# board.net
KiCad netlist of a schematic drawn in EAGLE
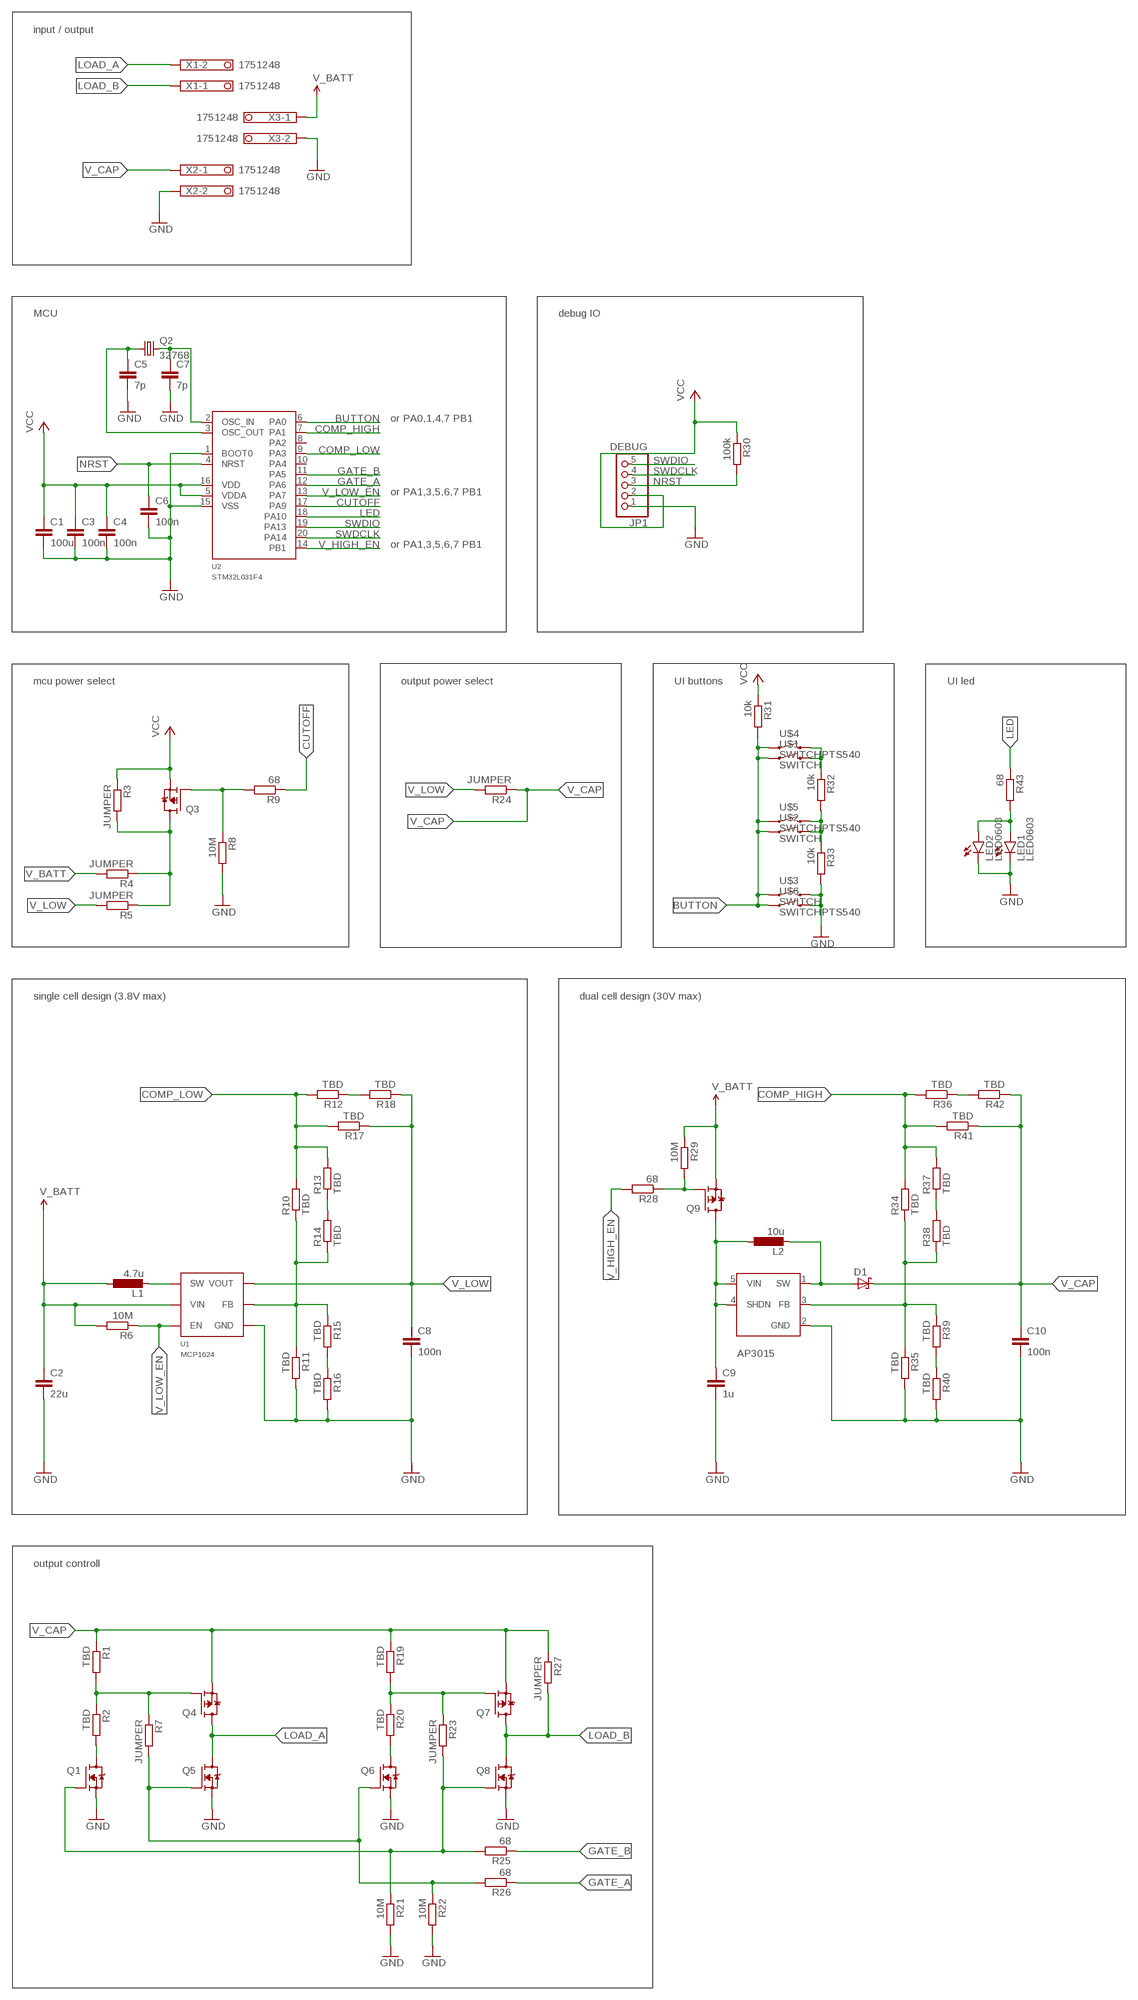
[diagram p0: schematic, sheet 1]

(export (version "E")
  (design (tool "Eeschema 10.0.6"))
  (components
    (comp (ref "C1")
      (value "100u")
      (footprint "eagle-import:1206-SMALL")
      (libsource (lib "eagle-import") (part "CAPACITOR1206"))
    )
    (comp (ref "C2")
      (value "22u")
      (footprint "eagle-import:0805-SMALL")
      (libsource (lib "eagle-import") (part "CAPACITOR0805"))
    )
    (comp (ref "C3")
      (value "100n")
      (footprint "eagle-import:0603-SMALL")
      (libsource (lib "eagle-import") (part "CAPACITOR0603"))
    )
    (comp (ref "C4")
      (value "100n")
      (footprint "eagle-import:0603-SMALL")
      (libsource (lib "eagle-import") (part "CAPACITOR0603"))
    )
    (comp (ref "C5")
      (value "7p")
      (footprint "eagle-import:0603-SMALL")
      (libsource (lib "eagle-import") (part "C-EU0603-SAMLL"))
    )
    (comp (ref "C6")
      (value "100n")
      (footprint "eagle-import:0603-SMALL")
      (libsource (lib "eagle-import") (part "CAPACITOR0603"))
    )
    (comp (ref "C7")
      (value "7p")
      (footprint "eagle-import:0603-SMALL")
      (libsource (lib "eagle-import") (part "C-EU0603-SAMLL"))
    )
    (comp (ref "C8")
      (value "100n")
      (footprint "eagle-import:0603-SMALL")
      (libsource (lib "eagle-import") (part "CAPACITOR0603"))
    )
    (comp (ref "C9")
      (value "1u")
      (footprint "eagle-import:0805-SMALL")
      (libsource (lib "eagle-import") (part "CAPACITOR0805"))
    )
    (comp (ref "C10")
      (value "100n")
      (footprint "eagle-import:0603-SMALL")
      (libsource (lib "eagle-import") (part "CAPACITOR0603"))
    )
    (comp (ref "D1")
      (value "SCHOTTKY")
      (footprint "eagle-import:DO-214")
      (libsource (lib "eagle-import") (part "SCHOTTKY"))
    )
    (comp (ref "JP1")
      (value "DEBUG")
      (footprint "eagle-import:1X05-S")
      (libsource (lib "eagle-import") (part "PINHD-1X05_2.54-S"))
    )
    (comp (ref "L1")
      (value "4.7u")
      (footprint "eagle-import:SRN2510F")
      (libsource (lib "eagle-import") (part "INDUCTORSRN2510F"))
    )
    (comp (ref "L2")
      (value "10u")
      (footprint "eagle-import:74404043100A")
      (libsource (lib "eagle-import") (part "INDUCTOR74404043100A"))
    )
    (comp (ref "LED1")
      (value "LED0603")
      (footprint "eagle-import:0603-SMALL")
      (libsource (lib "eagle-import") (part "LED0603"))
    )
    (comp (ref "LED2")
      (value "LED0603")
      (footprint "eagle-import:0603-SMALL")
      (libsource (lib "eagle-import") (part "LED0603"))
    )
    (comp (ref "Q1")
      (value "NFETGENERIC")
      (footprint "eagle-import:SOT23")
      (libsource (lib "eagle-import") (part "NFETGENERIC"))
    )
    (comp (ref "Q2")
      (value "32768")
      (footprint "eagle-import:ABS07")
      (libsource (lib "eagle-import") (part "ABS07"))
    )
    (comp (ref "Q3")
      (value "PFETIRLML6401")
      (footprint "eagle-import:SOT23")
      (libsource (lib "eagle-import") (part "PFETIRLML6401"))
    )
    (comp (ref "Q4")
      (value "PFETIRLML6401")
      (footprint "eagle-import:SOT23")
      (libsource (lib "eagle-import") (part "PFETIRLML6401"))
    )
    (comp (ref "Q5")
      (value "NFETGENERIC")
      (footprint "eagle-import:SOT23")
      (libsource (lib "eagle-import") (part "NFETGENERIC"))
    )
    (comp (ref "Q6")
      (value "NFETGENERIC")
      (footprint "eagle-import:SOT23")
      (libsource (lib "eagle-import") (part "NFETGENERIC"))
    )
    (comp (ref "Q7")
      (value "PFETIRLML6401")
      (footprint "eagle-import:SOT23")
      (libsource (lib "eagle-import") (part "PFETIRLML6401"))
    )
    (comp (ref "Q8")
      (value "NFETGENERIC")
      (footprint "eagle-import:SOT23")
      (libsource (lib "eagle-import") (part "NFETGENERIC"))
    )
    (comp (ref "Q9")
      (value "PFETIRLML6401")
      (footprint "eagle-import:SOT23")
      (libsource (lib "eagle-import") (part "PFETIRLML6401"))
    )
    (comp (ref "R1")
      (value "TBD")
      (footprint "eagle-import:0603-SMALL")
      (libsource (lib "eagle-import") (part "RESISTOR0603"))
    )
    (comp (ref "R2")
      (value "TBD")
      (footprint "eagle-import:0603-SMALL")
      (libsource (lib "eagle-import") (part "RESISTOR0603"))
    )
    (comp (ref "R3")
      (value "JUMPER")
      (footprint "eagle-import:0603-SMALL")
      (libsource (lib "eagle-import") (part "RESISTOR0603"))
    )
    (comp (ref "R4")
      (value "JUMPER")
      (footprint "eagle-import:0603-SMALL")
      (libsource (lib "eagle-import") (part "RESISTOR0603"))
    )
    (comp (ref "R5")
      (value "JUMPER")
      (footprint "eagle-import:0603-SMALL")
      (libsource (lib "eagle-import") (part "RESISTOR0603"))
    )
    (comp (ref "R6")
      (value "10M")
      (footprint "eagle-import:0603-SMALL")
      (libsource (lib "eagle-import") (part "RESISTOR0603"))
    )
    (comp (ref "R7")
      (value "JUMPER")
      (footprint "eagle-import:0603-SMALL")
      (libsource (lib "eagle-import") (part "RESISTOR0603"))
    )
    (comp (ref "R8")
      (value "10M")
      (footprint "eagle-import:0603-SMALL")
      (libsource (lib "eagle-import") (part "RESISTOR0603"))
    )
    (comp (ref "R9")
      (value "68")
      (footprint "eagle-import:0603-SMALL")
      (libsource (lib "eagle-import") (part "RESISTOR0603"))
    )
    (comp (ref "R10")
      (value "TBD")
      (footprint "eagle-import:0603-SMALL")
      (libsource (lib "eagle-import") (part "RESISTOR0603"))
    )
    (comp (ref "R11")
      (value "TBD")
      (footprint "eagle-import:0603-SMALL")
      (libsource (lib "eagle-import") (part "RESISTOR0603"))
    )
    (comp (ref "R12")
      (value "TBD")
      (footprint "eagle-import:0603-SMALL")
      (libsource (lib "eagle-import") (part "RESISTOR0603"))
    )
    (comp (ref "R13")
      (value "TBD")
      (footprint "eagle-import:0603-SMALL")
      (libsource (lib "eagle-import") (part "RESISTOR0603"))
    )
    (comp (ref "R14")
      (value "TBD")
      (footprint "eagle-import:0603-SMALL")
      (libsource (lib "eagle-import") (part "RESISTOR0603"))
    )
    (comp (ref "R15")
      (value "TBD")
      (footprint "eagle-import:0603-SMALL")
      (libsource (lib "eagle-import") (part "RESISTOR0603"))
    )
    (comp (ref "R16")
      (value "TBD")
      (footprint "eagle-import:0603-SMALL")
      (libsource (lib "eagle-import") (part "RESISTOR0603"))
    )
    (comp (ref "R17")
      (value "TBD")
      (footprint "eagle-import:0603-SMALL")
      (libsource (lib "eagle-import") (part "RESISTOR0603"))
    )
    (comp (ref "R18")
      (value "TBD")
      (footprint "eagle-import:0603-SMALL")
      (libsource (lib "eagle-import") (part "RESISTOR0603"))
    )
    (comp (ref "R19")
      (value "TBD")
      (footprint "eagle-import:0603-SMALL")
      (libsource (lib "eagle-import") (part "RESISTOR0603"))
    )
    (comp (ref "R20")
      (value "TBD")
      (footprint "eagle-import:0603-SMALL")
      (libsource (lib "eagle-import") (part "RESISTOR0603"))
    )
    (comp (ref "R21")
      (value "10M")
      (footprint "eagle-import:0603-SMALL")
      (libsource (lib "eagle-import") (part "RESISTOR0603"))
    )
    (comp (ref "R22")
      (value "10M")
      (footprint "eagle-import:0603-SMALL")
      (libsource (lib "eagle-import") (part "RESISTOR0603"))
    )
    (comp (ref "R23")
      (value "JUMPER")
      (footprint "eagle-import:0603-SMALL")
      (libsource (lib "eagle-import") (part "RESISTOR0603"))
    )
    (comp (ref "R24")
      (value "JUMPER")
      (footprint "eagle-import:0603-SMALL")
      (libsource (lib "eagle-import") (part "RESISTOR0603"))
    )
    (comp (ref "R25")
      (value "68")
      (footprint "eagle-import:0603-SMALL")
      (libsource (lib "eagle-import") (part "RESISTOR0603"))
    )
    (comp (ref "R26")
      (value "68")
      (footprint "eagle-import:0603-SMALL")
      (libsource (lib "eagle-import") (part "RESISTOR0603"))
    )
    (comp (ref "R27")
      (value "JUMPER")
      (footprint "eagle-import:0603-SMALL")
      (libsource (lib "eagle-import") (part "RESISTOR0603"))
    )
    (comp (ref "R28")
      (value "68")
      (footprint "eagle-import:0603-SMALL")
      (libsource (lib "eagle-import") (part "RESISTOR0603"))
    )
    (comp (ref "R29")
      (value "10M")
      (footprint "eagle-import:0603-SMALL")
      (libsource (lib "eagle-import") (part "RESISTOR0603"))
    )
    (comp (ref "R30")
      (value "100k")
      (footprint "eagle-import:0603-SMALL")
      (libsource (lib "eagle-import") (part "RESISTOR0603"))
    )
    (comp (ref "R31")
      (value "10k")
      (footprint "eagle-import:0603-SMALL")
      (libsource (lib "eagle-import") (part "RESISTOR0603"))
    )
    (comp (ref "R32")
      (value "10k")
      (footprint "eagle-import:0603-SMALL")
      (libsource (lib "eagle-import") (part "RESISTOR0603"))
    )
    (comp (ref "R33")
      (value "10k")
      (footprint "eagle-import:0603-SMALL")
      (libsource (lib "eagle-import") (part "RESISTOR0603"))
    )
    (comp (ref "R34")
      (value "TBD")
      (footprint "eagle-import:0603-SMALL")
      (libsource (lib "eagle-import") (part "RESISTOR0603"))
    )
    (comp (ref "R35")
      (value "TBD")
      (footprint "eagle-import:0603-SMALL")
      (libsource (lib "eagle-import") (part "RESISTOR0603"))
    )
    (comp (ref "R36")
      (value "TBD")
      (footprint "eagle-import:0603-SMALL")
      (libsource (lib "eagle-import") (part "RESISTOR0603"))
    )
    (comp (ref "R37")
      (value "TBD")
      (footprint "eagle-import:0603-SMALL")
      (libsource (lib "eagle-import") (part "RESISTOR0603"))
    )
    (comp (ref "R38")
      (value "TBD")
      (footprint "eagle-import:0603-SMALL")
      (libsource (lib "eagle-import") (part "RESISTOR0603"))
    )
    (comp (ref "R39")
      (value "TBD")
      (footprint "eagle-import:0603-SMALL")
      (libsource (lib "eagle-import") (part "RESISTOR0603"))
    )
    (comp (ref "R40")
      (value "TBD")
      (footprint "eagle-import:0603-SMALL")
      (libsource (lib "eagle-import") (part "RESISTOR0603"))
    )
    (comp (ref "R41")
      (value "TBD")
      (footprint "eagle-import:0603-SMALL")
      (libsource (lib "eagle-import") (part "RESISTOR0603"))
    )
    (comp (ref "R42")
      (value "TBD")
      (footprint "eagle-import:0603-SMALL")
      (libsource (lib "eagle-import") (part "RESISTOR0603"))
    )
    (comp (ref "R43")
      (value "68")
      (footprint "eagle-import:0603-SMALL")
      (libsource (lib "eagle-import") (part "RESISTOR0603"))
    )
    (comp (ref "U$1")
      (value "SWITCH")
      (footprint "eagle-import:TACT-4.6X2.8")
      (libsource (lib "eagle-import") (part "SWITCH"))
    )
    (comp (ref "U$2")
      (value "SWITCH")
      (footprint "eagle-import:TACT-4.6X2.8")
      (libsource (lib "eagle-import") (part "SWITCH"))
    )
    (comp (ref "U$3")
      (value "SWITCH")
      (footprint "eagle-import:TACT-4.6X2.8")
      (libsource (lib "eagle-import") (part "SWITCH"))
    )
    (comp (ref "U$4")
      (value "SWITCHPTS540")
      (footprint "eagle-import:PTS540")
      (libsource (lib "eagle-import") (part "SWITCHPTS540"))
    )
    (comp (ref "U$5")
      (value "SWITCHPTS540")
      (footprint "eagle-import:PTS540")
      (libsource (lib "eagle-import") (part "SWITCHPTS540"))
    )
    (comp (ref "U$6")
      (value "SWITCHPTS540")
      (footprint "eagle-import:PTS540")
      (libsource (lib "eagle-import") (part "SWITCHPTS540"))
    )
    (comp (ref "U1")
      (value "MCP1624")
      (footprint "eagle-import:SOT23-6")
      (libsource (lib "eagle-import") (part "MCP1624"))
    )
    (comp (ref "U2")
      (value "STM32L031F4")
      (footprint "eagle-import:TSSOP20")
      (libsource (lib "eagle-import") (part "STM32L031F4"))
    )
    (comp (ref "U3")
      (value "AP3015")
      (footprint "eagle-import:SOT23-5")
      (libsource (lib "eagle-import") (part "AP3015"))
    )
    (comp (ref "X1")
      (value "1751248")
      (footprint "eagle-import:1751248")
      (libsource (lib "eagle-import") (part "1751248"))
    )
    (comp (ref "X2")
      (value "1751248")
      (footprint "eagle-import:1751248")
      (libsource (lib "eagle-import") (part "1751248"))
    )
    (comp (ref "X3")
      (value "1751248")
      (footprint "eagle-import:1751248")
      (libsource (lib "eagle-import") (part "1751248"))
    )
  )
  (nets
    (net (code "1") (name "/SWDCLK") (class "Default")
      (node (ref "JP1") (pin "4") (pinfunction "4_4") (pintype "passive"))
      (node (ref "U2") (pin "20") (pinfunction "PA14_20") (pintype "bidirectional"))
    )
    (net (code "2") (name "/SWDIO") (class "Default")
      (node (ref "JP1") (pin "5") (pinfunction "5_5") (pintype "passive"))
      (node (ref "U2") (pin "19") (pinfunction "PA13_19") (pintype "bidirectional"))
    )
    (net (code "3") (name "BUTTON") (class "Default")
      (node (ref "R31") (pin "2") (pinfunction "2_2") (pintype "passive"))
      (node (ref "U$1") (pin "P$1") (pinfunction "1_P$1") (pintype "passive"))
      (node (ref "U$1") (pin "P$2") (pinfunction "1_P$2") (pintype "passive"))
      (node (ref "U$2") (pin "P$1") (pinfunction "1_P$1") (pintype "passive"))
      (node (ref "U$2") (pin "P$2") (pinfunction "1_P$2") (pintype "passive"))
      (node (ref "U$3") (pin "P$1") (pinfunction "1_P$1") (pintype "passive"))
      (node (ref "U$3") (pin "P$2") (pinfunction "1_P$2") (pintype "passive"))
      (node (ref "U$4") (pin "1") (pinfunction "1_1") (pintype "passive"))
      (node (ref "U$4") (pin "2") (pinfunction "1_2") (pintype "passive"))
      (node (ref "U$5") (pin "1") (pinfunction "1_1") (pintype "passive"))
      (node (ref "U$5") (pin "2") (pinfunction "1_2") (pintype "passive"))
      (node (ref "U$6") (pin "1") (pinfunction "1_1") (pintype "passive"))
      (node (ref "U$6") (pin "2") (pinfunction "1_2") (pintype "passive"))
      (node (ref "U2") (pin "6") (pinfunction "PA0_6") (pintype "bidirectional"))
    )
    (net (code "4") (name "COMP_HIGH") (class "Default")
      (node (ref "R34") (pin "2") (pinfunction "2_2") (pintype "passive"))
      (node (ref "R36") (pin "2") (pinfunction "2_2") (pintype "passive"))
      (node (ref "R37") (pin "2") (pinfunction "2_2") (pintype "passive"))
      (node (ref "R41") (pin "2") (pinfunction "2_2") (pintype "passive"))
      (node (ref "U2") (pin "7") (pinfunction "PA1_7") (pintype "bidirectional"))
    )
    (net (code "5") (name "COMP_LOW") (class "Default")
      (node (ref "R10") (pin "2") (pinfunction "2_2") (pintype "passive"))
      (node (ref "R12") (pin "2") (pinfunction "2_2") (pintype "passive"))
      (node (ref "R13") (pin "2") (pinfunction "2_2") (pintype "passive"))
      (node (ref "R17") (pin "2") (pinfunction "2_2") (pintype "passive"))
      (node (ref "U2") (pin "9") (pinfunction "PA3_9") (pintype "bidirectional"))
    )
    (net (code "6") (name "CUTOFF") (class "Default")
      (node (ref "R9") (pin "1") (pinfunction "1_1") (pintype "passive"))
      (node (ref "U2") (pin "17") (pinfunction "PA9_17") (pintype "bidirectional"))
    )
    (net (code "7") (name "GATE_A") (class "Default")
      (node (ref "R26") (pin "1") (pinfunction "1_1") (pintype "passive"))
      (node (ref "U2") (pin "12") (pinfunction "PA6_12") (pintype "bidirectional"))
    )
    (net (code "8") (name "GATE_B") (class "Default")
      (node (ref "R25") (pin "1") (pinfunction "1_1") (pintype "passive"))
      (node (ref "U2") (pin "11") (pinfunction "PA5_11") (pintype "bidirectional"))
    )
    (net (code "9") (name "GND") (class "Default")
      (node (ref "C1") (pin "2") (pinfunction "2_2") (pintype "passive"))
      (node (ref "C10") (pin "2") (pinfunction "2_2") (pintype "passive"))
      (node (ref "C2") (pin "2") (pinfunction "2_2") (pintype "passive"))
      (node (ref "C3") (pin "2") (pinfunction "2_2") (pintype "passive"))
      (node (ref "C4") (pin "2") (pinfunction "2_2") (pintype "passive"))
      (node (ref "C5") (pin "2") (pinfunction "2_2") (pintype "passive"))
      (node (ref "C6") (pin "2") (pinfunction "2_2") (pintype "passive"))
      (node (ref "C7") (pin "2") (pinfunction "2_2") (pintype "passive"))
      (node (ref "C8") (pin "2") (pinfunction "2_2") (pintype "passive"))
      (node (ref "C9") (pin "2") (pinfunction "2_2") (pintype "passive"))
      (node (ref "JP1") (pin "1") (pinfunction "1_1") (pintype "passive"))
      (node (ref "LED1") (pin "2") (pinfunction "C_2") (pintype "passive"))
      (node (ref "LED2") (pin "2") (pinfunction "C_2") (pintype "passive"))
      (node (ref "Q1") (pin "2") (pinfunction "S_2") (pintype "passive"))
      (node (ref "Q5") (pin "2") (pinfunction "S_2") (pintype "passive"))
      (node (ref "Q6") (pin "2") (pinfunction "S_2") (pintype "passive"))
      (node (ref "Q8") (pin "2") (pinfunction "S_2") (pintype "passive"))
      (node (ref "R11") (pin "2") (pinfunction "2_2") (pintype "passive"))
      (node (ref "R16") (pin "2") (pinfunction "2_2") (pintype "passive"))
      (node (ref "R21") (pin "2") (pinfunction "2_2") (pintype "passive"))
      (node (ref "R22") (pin "2") (pinfunction "2_2") (pintype "passive"))
      (node (ref "R33") (pin "2") (pinfunction "2_2") (pintype "passive"))
      (node (ref "R35") (pin "2") (pinfunction "2_2") (pintype "passive"))
      (node (ref "R40") (pin "2") (pinfunction "2_2") (pintype "passive"))
      (node (ref "R8") (pin "2") (pinfunction "2_2") (pintype "passive"))
      (node (ref "U$3") (pin "P$3") (pinfunction "2_P$3") (pintype "passive"))
      (node (ref "U$3") (pin "P$4") (pinfunction "2_P$4") (pintype "passive"))
      (node (ref "U$6") (pin "3") (pinfunction "2_3") (pintype "passive"))
      (node (ref "U$6") (pin "4") (pinfunction "2_4") (pintype "passive"))
      (node (ref "U1") (pin "2") (pinfunction "GND_2") (pintype "bidirectional"))
      (node (ref "U2") (pin "1") (pinfunction "BOOT0_1") (pintype "bidirectional"))
      (node (ref "U2") (pin "15") (pinfunction "VSS_15") (pintype "bidirectional"))
      (node (ref "U3") (pin "2") (pinfunction "GND_2") (pintype "bidirectional"))
      (node (ref "X2") (pin "2") (pinfunction "K_2") (pintype "passive"))
      (node (ref "X3") (pin "2") (pinfunction "K_2") (pintype "passive"))
    )
    (net (code "10") (name "LED") (class "Default")
      (node (ref "R43") (pin "1") (pinfunction "1_1") (pintype "passive"))
      (node (ref "U2") (pin "18") (pinfunction "PA10_18") (pintype "bidirectional"))
    )
    (net (code "11") (name "LOAD_A") (class "Default")
      (node (ref "Q4") (pin "3") (pinfunction "D_3") (pintype "passive"))
      (node (ref "Q5") (pin "3") (pinfunction "D_3") (pintype "passive"))
      (node (ref "X1") (pin "2") (pinfunction "K_2") (pintype "passive"))
    )
    (net (code "12") (name "LOAD_B") (class "Default")
      (node (ref "Q7") (pin "3") (pinfunction "D_3") (pintype "passive"))
      (node (ref "Q8") (pin "3") (pinfunction "D_3") (pintype "passive"))
      (node (ref "R27") (pin "2") (pinfunction "2_2") (pintype "passive"))
      (node (ref "X1") (pin "1") (pinfunction "K_1") (pintype "passive"))
    )
    (net (code "13") (name "NRST") (class "Default")
      (node (ref "C6") (pin "1") (pinfunction "1_1") (pintype "passive"))
      (node (ref "JP1") (pin "3") (pinfunction "3_3") (pintype "passive"))
      (node (ref "R30") (pin "2") (pinfunction "2_2") (pintype "passive"))
      (node (ref "U2") (pin "4") (pinfunction "NRST_4") (pintype "bidirectional"))
    )
    (net (code "14") (name "Net-(D1-A)") (class "Default")
      (node (ref "D1") (pin "P$1") (pinfunction "A_P$1") (pintype "passive"))
      (node (ref "L2") (pin "P$2") (pinfunction "2_P$2") (pintype "passive"))
      (node (ref "U3") (pin "1") (pinfunction "SW_1") (pintype "bidirectional"))
    )
    (net (code "15") (name "Net-(L1-2)") (class "Default")
      (node (ref "L1") (pin "P$2") (pinfunction "2_P$2") (pintype "passive"))
      (node (ref "U1") (pin "1") (pinfunction "SW_1") (pintype "bidirectional"))
    )
    (net (code "16") (name "Net-(L2-1)") (class "Default")
      (node (ref "C9") (pin "1") (pinfunction "1_1") (pintype "passive"))
      (node (ref "L2") (pin "P$1") (pinfunction "1_P$1") (pintype "passive"))
      (node (ref "Q9") (pin "3") (pinfunction "D_3") (pintype "passive"))
      (node (ref "U3") (pin "4") (pinfunction "SHDN_4") (pintype "bidirectional"))
      (node (ref "U3") (pin "5") (pinfunction "VIN_5") (pintype "bidirectional"))
    )
    (net (code "17") (name "Net-(LED1-A)") (class "Default")
      (node (ref "LED1") (pin "1") (pinfunction "A_1") (pintype "passive"))
      (node (ref "LED2") (pin "1") (pinfunction "A_1") (pintype "passive"))
      (node (ref "R43") (pin "2") (pinfunction "2_2") (pintype "passive"))
    )
    (net (code "18") (name "Net-(Q1-D)") (class "Default")
      (node (ref "Q1") (pin "3") (pinfunction "D_3") (pintype "passive"))
      (node (ref "R2") (pin "2") (pinfunction "2_2") (pintype "passive"))
    )
    (net (code "19") (name "Net-(Q1-G)") (class "Default")
      (node (ref "Q1") (pin "1") (pinfunction "G_1") (pintype "passive"))
      (node (ref "Q8") (pin "1") (pinfunction "G_1") (pintype "passive"))
      (node (ref "R21") (pin "1") (pinfunction "1_1") (pintype "passive"))
      (node (ref "R23") (pin "2") (pinfunction "2_2") (pintype "passive"))
      (node (ref "R25") (pin "2") (pinfunction "2_2") (pintype "passive"))
    )
    (net (code "20") (name "Net-(Q2-1)") (class "Default")
      (node (ref "C5") (pin "1") (pinfunction "1_1") (pintype "passive"))
      (node (ref "Q2") (pin "P$1") (pinfunction "1_P$1") (pintype "passive"))
      (node (ref "U2") (pin "3") (pinfunction "OSC_OUT_3") (pintype "bidirectional"))
    )
    (net (code "21") (name "Net-(Q2-2)") (class "Default")
      (node (ref "C7") (pin "1") (pinfunction "1_1") (pintype "passive"))
      (node (ref "Q2") (pin "P$2") (pinfunction "2_P$2") (pintype "passive"))
      (node (ref "U2") (pin "2") (pinfunction "OSC_IN_2") (pintype "bidirectional"))
    )
    (net (code "22") (name "Net-(Q3-D)") (class "Default")
      (node (ref "Q3") (pin "3") (pinfunction "D_3") (pintype "passive"))
      (node (ref "R3") (pin "2") (pinfunction "2_2") (pintype "passive"))
      (node (ref "R4") (pin "1") (pinfunction "1_1") (pintype "passive"))
      (node (ref "R5") (pin "1") (pinfunction "1_1") (pintype "passive"))
    )
    (net (code "23") (name "Net-(Q3-G)") (class "Default")
      (node (ref "Q3") (pin "1") (pinfunction "G_1") (pintype "passive"))
      (node (ref "R8") (pin "1") (pinfunction "1_1") (pintype "passive"))
      (node (ref "R9") (pin "2") (pinfunction "2_2") (pintype "passive"))
    )
    (net (code "24") (name "Net-(Q4-G)") (class "Default")
      (node (ref "Q4") (pin "1") (pinfunction "G_1") (pintype "passive"))
      (node (ref "R1") (pin "2") (pinfunction "2_2") (pintype "passive"))
      (node (ref "R2") (pin "1") (pinfunction "1_1") (pintype "passive"))
      (node (ref "R7") (pin "1") (pinfunction "1_1") (pintype "passive"))
    )
    (net (code "25") (name "Net-(Q5-G)") (class "Default")
      (node (ref "Q5") (pin "1") (pinfunction "G_1") (pintype "passive"))
      (node (ref "Q6") (pin "1") (pinfunction "G_1") (pintype "passive"))
      (node (ref "R22") (pin "1") (pinfunction "1_1") (pintype "passive"))
      (node (ref "R26") (pin "2") (pinfunction "2_2") (pintype "passive"))
      (node (ref "R7") (pin "2") (pinfunction "2_2") (pintype "passive"))
    )
    (net (code "26") (name "Net-(Q6-D)") (class "Default")
      (node (ref "Q6") (pin "3") (pinfunction "D_3") (pintype "passive"))
      (node (ref "R20") (pin "2") (pinfunction "2_2") (pintype "passive"))
    )
    (net (code "27") (name "Net-(Q7-G)") (class "Default")
      (node (ref "Q7") (pin "1") (pinfunction "G_1") (pintype "passive"))
      (node (ref "R19") (pin "2") (pinfunction "2_2") (pintype "passive"))
      (node (ref "R20") (pin "1") (pinfunction "1_1") (pintype "passive"))
      (node (ref "R23") (pin "1") (pinfunction "1_1") (pintype "passive"))
    )
    (net (code "28") (name "Net-(Q9-G)") (class "Default")
      (node (ref "Q9") (pin "1") (pinfunction "G_1") (pintype "passive"))
      (node (ref "R28") (pin "1") (pinfunction "1_1") (pintype "passive"))
      (node (ref "R29") (pin "2") (pinfunction "2_2") (pintype "passive"))
    )
    (net (code "29") (name "Net-(R12-Pad1)") (class "Default")
      (node (ref "R12") (pin "1") (pinfunction "1_1") (pintype "passive"))
      (node (ref "R18") (pin "2") (pinfunction "2_2") (pintype "passive"))
    )
    (net (code "30") (name "Net-(R13-Pad1)") (class "Default")
      (node (ref "R13") (pin "1") (pinfunction "1_1") (pintype "passive"))
      (node (ref "R14") (pin "2") (pinfunction "2_2") (pintype "passive"))
    )
    (net (code "31") (name "Net-(R15-Pad2)") (class "Default")
      (node (ref "R15") (pin "2") (pinfunction "2_2") (pintype "passive"))
      (node (ref "R16") (pin "1") (pinfunction "1_1") (pintype "passive"))
    )
    (net (code "32") (name "Net-(R32-Pad1)") (class "Default")
      (node (ref "R32") (pin "1") (pinfunction "1_1") (pintype "passive"))
      (node (ref "U$1") (pin "P$3") (pinfunction "2_P$3") (pintype "passive"))
      (node (ref "U$1") (pin "P$4") (pinfunction "2_P$4") (pintype "passive"))
      (node (ref "U$4") (pin "3") (pinfunction "2_3") (pintype "passive"))
      (node (ref "U$4") (pin "4") (pinfunction "2_4") (pintype "passive"))
    )
    (net (code "33") (name "Net-(R32-Pad2)") (class "Default")
      (node (ref "R32") (pin "2") (pinfunction "2_2") (pintype "passive"))
      (node (ref "R33") (pin "1") (pinfunction "1_1") (pintype "passive"))
      (node (ref "U$2") (pin "P$3") (pinfunction "2_P$3") (pintype "passive"))
      (node (ref "U$2") (pin "P$4") (pinfunction "2_P$4") (pintype "passive"))
      (node (ref "U$5") (pin "3") (pinfunction "2_3") (pintype "passive"))
      (node (ref "U$5") (pin "4") (pinfunction "2_4") (pintype "passive"))
    )
    (net (code "34") (name "Net-(R36-Pad1)") (class "Default")
      (node (ref "R36") (pin "1") (pinfunction "1_1") (pintype "passive"))
      (node (ref "R42") (pin "2") (pinfunction "2_2") (pintype "passive"))
    )
    (net (code "35") (name "Net-(R37-Pad1)") (class "Default")
      (node (ref "R37") (pin "1") (pinfunction "1_1") (pintype "passive"))
      (node (ref "R38") (pin "2") (pinfunction "2_2") (pintype "passive"))
    )
    (net (code "36") (name "Net-(R39-Pad2)") (class "Default")
      (node (ref "R39") (pin "2") (pinfunction "2_2") (pintype "passive"))
      (node (ref "R40") (pin "1") (pinfunction "1_1") (pintype "passive"))
    )
    (net (code "37") (name "Net-(U1-FB)") (class "Default")
      (node (ref "R10") (pin "1") (pinfunction "1_1") (pintype "passive"))
      (node (ref "R11") (pin "1") (pinfunction "1_1") (pintype "passive"))
      (node (ref "R14") (pin "1") (pinfunction "1_1") (pintype "passive"))
      (node (ref "R15") (pin "1") (pinfunction "1_1") (pintype "passive"))
      (node (ref "U1") (pin "4") (pinfunction "FB_4") (pintype "bidirectional"))
    )
    (net (code "38") (name "Net-(U3-FB)") (class "Default")
      (node (ref "R34") (pin "1") (pinfunction "1_1") (pintype "passive"))
      (node (ref "R35") (pin "1") (pinfunction "1_1") (pintype "passive"))
      (node (ref "R38") (pin "1") (pinfunction "1_1") (pintype "passive"))
      (node (ref "R39") (pin "1") (pinfunction "1_1") (pintype "passive"))
      (node (ref "U3") (pin "3") (pinfunction "FB_3") (pintype "bidirectional"))
    )
    (net (code "39") (name "VCC") (class "Default")
      (node (ref "C1") (pin "1") (pinfunction "1_1") (pintype "passive"))
      (node (ref "C3") (pin "1") (pinfunction "1_1") (pintype "passive"))
      (node (ref "C4") (pin "1") (pinfunction "1_1") (pintype "passive"))
      (node (ref "JP1") (pin "2") (pinfunction "2_2") (pintype "passive"))
      (node (ref "Q3") (pin "2") (pinfunction "S_2") (pintype "passive"))
      (node (ref "R3") (pin "1") (pinfunction "1_1") (pintype "passive"))
      (node (ref "R30") (pin "1") (pinfunction "1_1") (pintype "passive"))
      (node (ref "R31") (pin "1") (pinfunction "1_1") (pintype "passive"))
      (node (ref "U2") (pin "16") (pinfunction "VDD_16") (pintype "bidirectional"))
      (node (ref "U2") (pin "5") (pinfunction "VDDA_5") (pintype "bidirectional"))
    )
    (net (code "40") (name "V_BATT") (class "Default")
      (node (ref "C2") (pin "1") (pinfunction "1_1") (pintype "passive"))
      (node (ref "L1") (pin "P$1") (pinfunction "1_P$1") (pintype "passive"))
      (node (ref "Q9") (pin "2") (pinfunction "S_2") (pintype "passive"))
      (node (ref "R29") (pin "1") (pinfunction "1_1") (pintype "passive"))
      (node (ref "R4") (pin "2") (pinfunction "2_2") (pintype "passive"))
      (node (ref "R6") (pin "2") (pinfunction "2_2") (pintype "passive"))
      (node (ref "U1") (pin "6") (pinfunction "VIN_6") (pintype "bidirectional"))
      (node (ref "X3") (pin "1") (pinfunction "K_1") (pintype "passive"))
    )
    (net (code "41") (name "V_CAP") (class "Default")
      (node (ref "C10") (pin "1") (pinfunction "1_1") (pintype "passive"))
      (node (ref "D1") (pin "P$2") (pinfunction "C_P$2") (pintype "passive"))
      (node (ref "Q4") (pin "2") (pinfunction "S_2") (pintype "passive"))
      (node (ref "Q7") (pin "2") (pinfunction "S_2") (pintype "passive"))
      (node (ref "R1") (pin "1") (pinfunction "1_1") (pintype "passive"))
      (node (ref "R19") (pin "1") (pinfunction "1_1") (pintype "passive"))
      (node (ref "R24") (pin "1") (pinfunction "1_1") (pintype "passive"))
      (node (ref "R27") (pin "1") (pinfunction "1_1") (pintype "passive"))
      (node (ref "R41") (pin "1") (pinfunction "1_1") (pintype "passive"))
      (node (ref "R42") (pin "1") (pinfunction "1_1") (pintype "passive"))
      (node (ref "X2") (pin "1") (pinfunction "K_1") (pintype "passive"))
    )
    (net (code "42") (name "V_HIGH_EN") (class "Default")
      (node (ref "R28") (pin "2") (pinfunction "2_2") (pintype "passive"))
      (node (ref "U2") (pin "14") (pinfunction "PB1_14") (pintype "bidirectional"))
    )
    (net (code "43") (name "V_LOW") (class "Default")
      (node (ref "C8") (pin "1") (pinfunction "1_1") (pintype "passive"))
      (node (ref "R17") (pin "1") (pinfunction "1_1") (pintype "passive"))
      (node (ref "R18") (pin "1") (pinfunction "1_1") (pintype "passive"))
      (node (ref "R24") (pin "2") (pinfunction "2_2") (pintype "passive"))
      (node (ref "R5") (pin "2") (pinfunction "2_2") (pintype "passive"))
      (node (ref "U1") (pin "5") (pinfunction "VOUT_5") (pintype "bidirectional"))
    )
    (net (code "44") (name "V_LOW_EN") (class "Default")
      (node (ref "R6") (pin "1") (pinfunction "1_1") (pintype "passive"))
      (node (ref "U1") (pin "3") (pinfunction "EN_3") (pintype "bidirectional"))
      (node (ref "U2") (pin "13") (pinfunction "PA7_13") (pintype "bidirectional"))
    )
    (net (code "45") (name "unconnected-(U2-PA2-Pad8)") (class "Default")
      (node (ref "U2") (pin "8") (pinfunction "PA2_8") (pintype "bidirectional"))
    )
    (net (code "46") (name "unconnected-(U2-PA4-Pad10)") (class "Default")
      (node (ref "U2") (pin "10") (pinfunction "PA4_10") (pintype "bidirectional"))
    )
  )
)
